# raspi.net
KiCad netlist of a schematic drawn in EAGLE
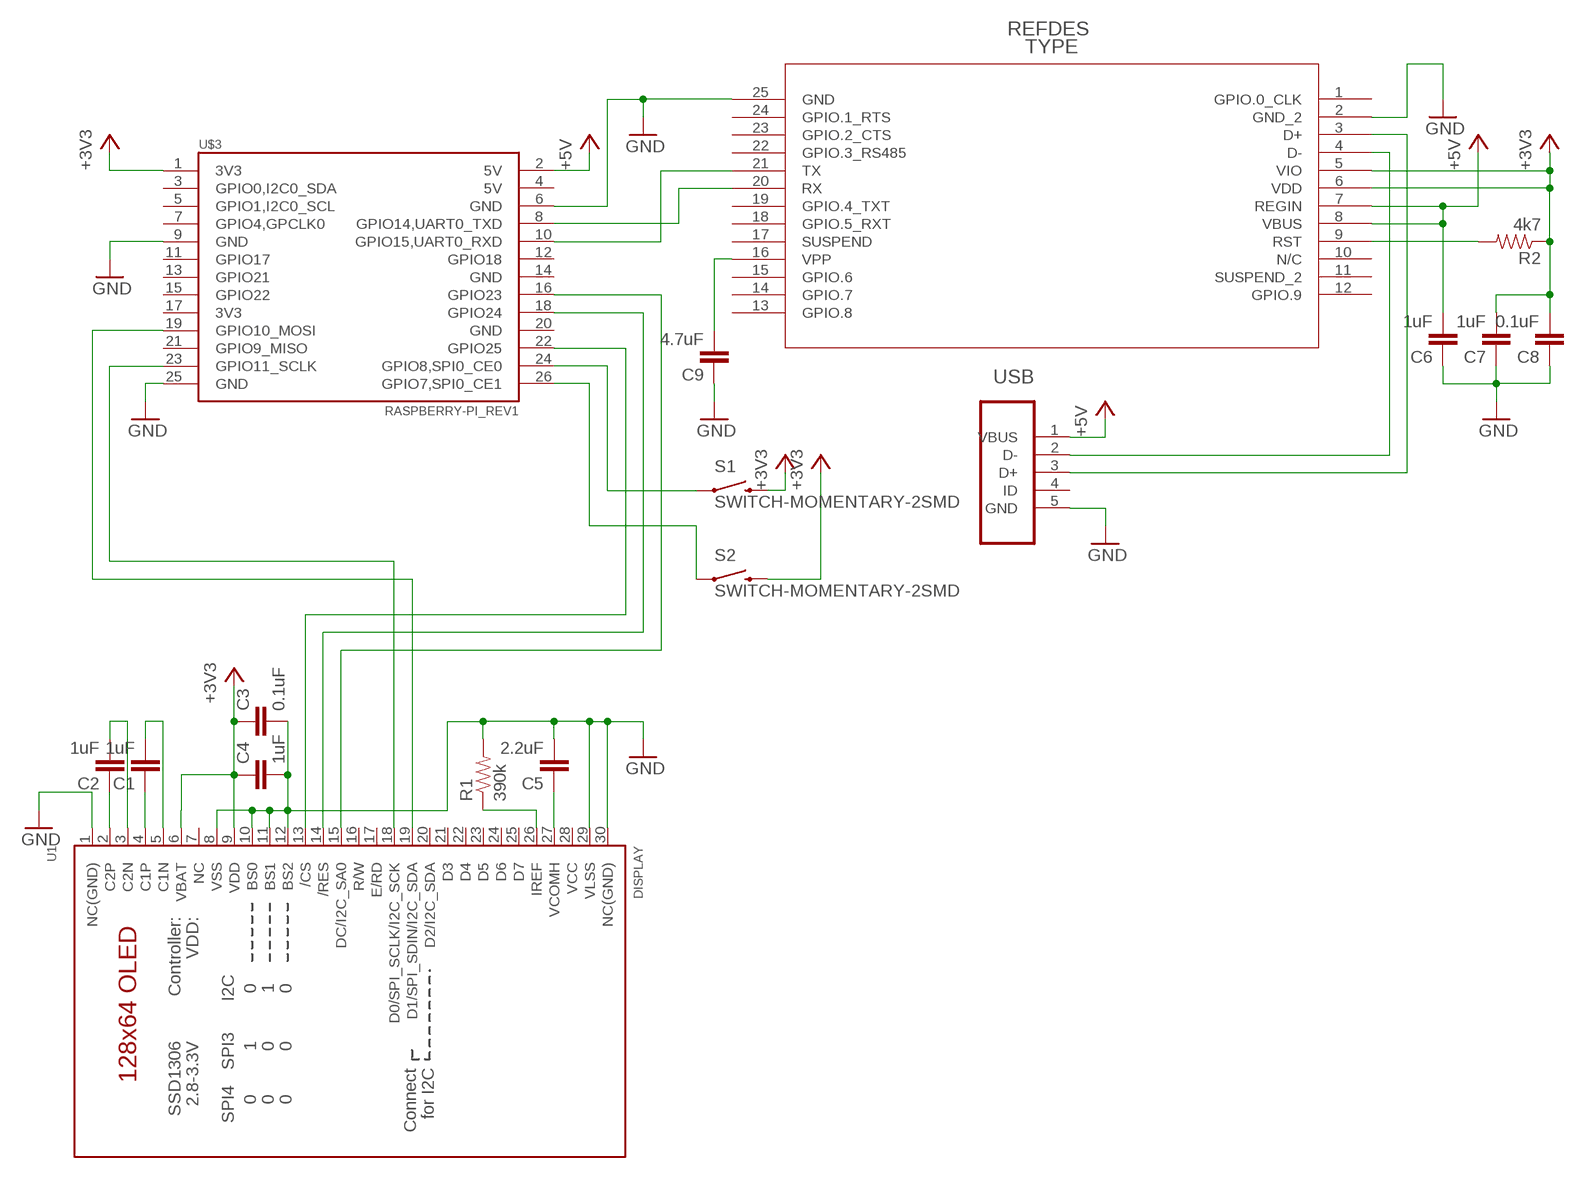
[diagram p0: schematic, sheet 1]

(export (version "E")
  (design (tool "Eeschema 10.0.6"))
  (components
    (comp (ref "C1")
      (value "1uF")
      (footprint "eagle-import:0805")
      (libsource (lib "eagle-import") (part "CAP0805"))
    )
    (comp (ref "C2")
      (value "1uF")
      (footprint "eagle-import:0805")
      (libsource (lib "eagle-import") (part "CAP0805"))
    )
    (comp (ref "C3")
      (value "0.1uF")
      (footprint "eagle-import:0805")
      (libsource (lib "eagle-import") (part "CAP0805"))
    )
    (comp (ref "C4")
      (value "1uF")
      (footprint "eagle-import:0805")
      (libsource (lib "eagle-import") (part "CAP0805"))
    )
    (comp (ref "C5")
      (value "2.2uF")
      (footprint "eagle-import:0805")
      (libsource (lib "eagle-import") (part "CAP0805"))
    )
    (comp (ref "C6")
      (value "1uF")
      (footprint "eagle-import:0805")
      (libsource (lib "eagle-import") (part "CAP0805"))
    )
    (comp (ref "C7")
      (value "1uF")
      (footprint "eagle-import:0805")
      (libsource (lib "eagle-import") (part "CAP0805"))
    )
    (comp (ref "C8")
      (value "0.1uF")
      (footprint "eagle-import:0805")
      (libsource (lib "eagle-import") (part "CAP0805"))
    )
    (comp (ref "C9")
      (value "4.7uF")
      (footprint "eagle-import:0805")
      (libsource (lib "eagle-import") (part "CAP0805"))
    )
    (comp (ref "R1")
      (value "390k")
      (footprint "eagle-import:0805")
      (libsource (lib "eagle-import") (part "RESISTOR0805-RES"))
    )
    (comp (ref "R2")
      (value "4k7")
      (footprint "eagle-import:0805")
      (libsource (lib "eagle-import") (part "RESISTOR0805-RES"))
    )
    (comp (ref "S1")
      (value "SWITCH-MOMENTARY-2SMD")
      (footprint "eagle-import:TACTILE_SWITCH_SMD")
      (libsource (lib "eagle-import") (part "SWITCH-MOMENTARY-2SMD"))
    )
    (comp (ref "S2")
      (value "SWITCH-MOMENTARY-2SMD")
      (footprint "eagle-import:TACTILE_SWITCH_SMD")
      (libsource (lib "eagle-import") (part "SWITCH-MOMENTARY-2SMD"))
    )
    (comp (ref "U$3")
      (value "RASPBERRY-PI_REV1")
      (footprint "eagle-import:RASPBERRY-PI_REV1")
      (libsource (lib "eagle-import") (part "RASPBERRY-PI_REV1"))
    )
    (comp (ref "U1")
      (value "DISPLAY")
      (footprint "eagle-import:UG-2864HSWEG01_0.96IN_WRAPAROUND")
      (libsource (lib "eagle-import") (part "DISP_OLED_UG-2864HSWEG010.96{dblquote}"))
    )
    (comp (ref "U2")
      (value "CP2110-F01-GM")
      (footprint "eagle-import:CP2110-F01-GM")
      (libsource (lib "eagle-import") (part "CP2110-F01-GM"))
    )
    (comp (ref "USB")
      (value "47346-0001")
      (footprint "eagle-import:MOLEX_47346-0001")
      (libsource (lib "eagle-import") (part "47346-0001"))
    )
  )
  (nets
    (net (code "1") (name "+3V3") (class "Default")
      (node (ref "C3") (pin "1") (pinfunction "1_1") (pintype "passive"))
      (node (ref "C4") (pin "1") (pinfunction "1_1") (pintype "passive"))
      (node (ref "C7") (pin "2") (pinfunction "2_2") (pintype "passive"))
      (node (ref "C8") (pin "2") (pinfunction "2_2") (pintype "passive"))
      (node (ref "R2") (pin "1") (pinfunction "1_1") (pintype "passive"))
      (node (ref "S1") (pin "3") (pinfunction "2_3") (pintype "passive"))
      (node (ref "S2") (pin "3") (pinfunction "2_3") (pintype "passive"))
      (node (ref "U$3") (pin "1") (pinfunction "3V3_1") (pintype "bidirectional"))
      (node (ref "U1") (pin "6") (pinfunction "VBAT_6") (pintype "input"))
      (node (ref "U1") (pin "9") (pinfunction "VDD_9") (pintype "power_in"))
      (node (ref "U2") (pin "5") (pinfunction "VIO_5") (pintype "passive"))
      (node (ref "U2") (pin "6") (pinfunction "VDD_6") (pintype "passive"))
    )
    (net (code "2") (name "+5V") (class "Default")
      (node (ref "C6") (pin "2") (pinfunction "2_2") (pintype "passive"))
      (node (ref "U$3") (pin "2") (pinfunction "5V_2") (pintype "bidirectional"))
      (node (ref "U2") (pin "7") (pinfunction "REGIN_7") (pintype "passive"))
      (node (ref "U2") (pin "8") (pinfunction "VBUS_8") (pintype "passive"))
      (node (ref "USB") (pin "1") (pinfunction "VBUS_1") (pintype "input"))
    )
    (net (code "3") (name "/VCC") (class "Default")
      (node (ref "U1") (pin "28") (pinfunction "VCC_28") (pintype "power_in"))
    )
    (net (code "4") (name "GND") (class "Default")
      (node (ref "C3") (pin "2") (pinfunction "2_2") (pintype "passive"))
      (node (ref "C4") (pin "2") (pinfunction "2_2") (pintype "passive"))
      (node (ref "C5") (pin "2") (pinfunction "2_2") (pintype "passive"))
      (node (ref "C6") (pin "1") (pinfunction "1_1") (pintype "passive"))
      (node (ref "C7") (pin "1") (pinfunction "1_1") (pintype "passive"))
      (node (ref "C8") (pin "1") (pinfunction "1_1") (pintype "passive"))
      (node (ref "C9") (pin "1") (pinfunction "1_1") (pintype "passive"))
      (node (ref "R1") (pin "2") (pinfunction "2_2") (pintype "passive"))
      (node (ref "U$3") (pin "25") (pinfunction "GND_25") (pintype "bidirectional"))
      (node (ref "U$3") (pin "6") (pinfunction "GND_6") (pintype "bidirectional"))
      (node (ref "U$3") (pin "9") (pinfunction "GND_9") (pintype "bidirectional"))
      (node (ref "U1") (pin "1") (pinfunction "NC(GND)_1") (pintype "input"))
      (node (ref "U1") (pin "10") (pinfunction "BS0_10") (pintype "input"))
      (node (ref "U1") (pin "11") (pinfunction "BS1_11") (pintype "input"))
      (node (ref "U1") (pin "12") (pinfunction "BS2_12") (pintype "input"))
      (node (ref "U1") (pin "29") (pinfunction "VLSS_29") (pintype "power_in"))
      (node (ref "U1") (pin "30") (pinfunction "NC(GND)_30") (pintype "input"))
      (node (ref "U1") (pin "8") (pinfunction "VSS_8") (pintype "power_in"))
      (node (ref "U2") (pin "2") (pinfunction "GND_2_2") (pintype "passive"))
      (node (ref "U2") (pin "25") (pinfunction "GND_25") (pintype "passive"))
      (node (ref "USB") (pin "5") (pinfunction "GND_5") (pintype "input"))
    )
    (net (code "5") (name "Net-(U$3-GPIO7,SPI0_CE1)") (class "Default")
      (node (ref "S2") (pin "1") (pinfunction "1_1") (pintype "passive"))
      (node (ref "U$3") (pin "26") (pinfunction "GPIO7,SPI0_CE1_26") (pintype "bidirectional"))
    )
    (net (code "6") (name "Net-(U$3-GPIO8,SPI0_CE0)") (class "Default")
      (node (ref "S1") (pin "1") (pinfunction "1_1") (pintype "passive"))
      (node (ref "U$3") (pin "24") (pinfunction "GPIO8,SPI0_CE0_24") (pintype "bidirectional"))
    )
    (net (code "7") (name "Net-(U$3-GPIO10_MOSI)") (class "Default")
      (node (ref "U$3") (pin "19") (pinfunction "GPIO10_MOSI_19") (pintype "bidirectional"))
      (node (ref "U1") (pin "19") (pinfunction "D1/SPI_SDIN/I2C_SDA_19") (pintype "bidirectional"))
    )
    (net (code "8") (name "Net-(U$3-GPIO11_SCLK)") (class "Default")
      (node (ref "U$3") (pin "23") (pinfunction "GPIO11_SCLK_23") (pintype "bidirectional"))
      (node (ref "U1") (pin "18") (pinfunction "D0/SPI_SCLK/I2C_SCK_18") (pintype "bidirectional"))
    )
    (net (code "9") (name "Net-(U$3-GPIO14,UART0_TXD)") (class "Default")
      (node (ref "U$3") (pin "8") (pinfunction "GPIO14,UART0_TXD_8") (pintype "bidirectional"))
      (node (ref "U2") (pin "20") (pinfunction "RX_20") (pintype "passive"))
    )
    (net (code "10") (name "Net-(U$3-GPIO15,UART0_RXD)") (class "Default")
      (node (ref "U$3") (pin "10") (pinfunction "GPIO15,UART0_RXD_10") (pintype "bidirectional"))
      (node (ref "U2") (pin "21") (pinfunction "TX_21") (pintype "passive"))
    )
    (net (code "11") (name "Net-(U$3-GPIO23)") (class "Default")
      (node (ref "U$3") (pin "16") (pinfunction "GPIO23_16") (pintype "bidirectional"))
      (node (ref "U1") (pin "15") (pinfunction "DC/I2C_SA0_15") (pintype "input"))
    )
    (net (code "12") (name "Net-(U$3-GPIO24)") (class "Default")
      (node (ref "U$3") (pin "18") (pinfunction "GPIO24_18") (pintype "bidirectional"))
      (node (ref "U1") (pin "14") (pinfunction "/RES_14") (pintype "input"))
    )
    (net (code "13") (name "Net-(U$3-GPIO25)") (class "Default")
      (node (ref "U$3") (pin "22") (pinfunction "GPIO25_22") (pintype "bidirectional"))
      (node (ref "U1") (pin "13") (pinfunction "/CS_13") (pintype "input"))
    )
    (net (code "14") (name "Net-(U1-C1N)") (class "Default")
      (node (ref "C1") (pin "2") (pinfunction "2_2") (pintype "passive"))
      (node (ref "U1") (pin "5") (pinfunction "C1N_5") (pintype "input"))
    )
    (net (code "15") (name "Net-(U1-C1P)") (class "Default")
      (node (ref "C1") (pin "1") (pinfunction "1_1") (pintype "passive"))
      (node (ref "U1") (pin "4") (pinfunction "C1P_4") (pintype "input"))
    )
    (net (code "16") (name "Net-(U1-C2N)") (class "Default")
      (node (ref "C2") (pin "2") (pinfunction "2_2") (pintype "passive"))
      (node (ref "U1") (pin "3") (pinfunction "C2N_3") (pintype "input"))
    )
    (net (code "17") (name "Net-(U1-C2P)") (class "Default")
      (node (ref "C2") (pin "1") (pinfunction "1_1") (pintype "passive"))
      (node (ref "U1") (pin "2") (pinfunction "C2P_2") (pintype "input"))
    )
    (net (code "18") (name "Net-(U1-IREF)") (class "Default")
      (node (ref "R1") (pin "1") (pinfunction "1_1") (pintype "passive"))
      (node (ref "U1") (pin "26") (pinfunction "IREF_26") (pintype "input"))
    )
    (net (code "19") (name "Net-(U1-VCOMH)") (class "Default")
      (node (ref "C5") (pin "1") (pinfunction "1_1") (pintype "passive"))
      (node (ref "U1") (pin "27") (pinfunction "VCOMH_27") (pintype "output"))
    )
    (net (code "20") (name "Net-(U2-D+)") (class "Default")
      (node (ref "U2") (pin "3") (pinfunction "D+_3") (pintype "passive"))
      (node (ref "USB") (pin "3") (pinfunction "D+_3") (pintype "input"))
    )
    (net (code "21") (name "Net-(U2-D-)") (class "Default")
      (node (ref "U2") (pin "4") (pinfunction "D-_4") (pintype "passive"))
      (node (ref "USB") (pin "2") (pinfunction "D-_2") (pintype "input"))
    )
    (net (code "22") (name "Net-(U2-RST)") (class "Default")
      (node (ref "R2") (pin "2") (pinfunction "2_2") (pintype "passive"))
      (node (ref "U2") (pin "9") (pinfunction "RST_9") (pintype "passive"))
    )
    (net (code "23") (name "Net-(U2-VPP)") (class "Default")
      (node (ref "C9") (pin "2") (pinfunction "2_2") (pintype "passive"))
      (node (ref "U2") (pin "16") (pinfunction "VPP_16") (pintype "passive"))
    )
    (net (code "24") (name "unconnected-(U$3-3V3-Pad17)") (class "Default")
      (node (ref "U$3") (pin "17") (pinfunction "3V3_17") (pintype "bidirectional"))
    )
    (net (code "25") (name "unconnected-(U$3-5V-Pad4)") (class "Default")
      (node (ref "U$3") (pin "4") (pinfunction "5V_4") (pintype "bidirectional"))
    )
    (net (code "26") (name "unconnected-(U$3-GND-Pad14)") (class "Default")
      (node (ref "U$3") (pin "14") (pinfunction "GND_14") (pintype "bidirectional"))
    )
    (net (code "27") (name "unconnected-(U$3-GND-Pad20)") (class "Default")
      (node (ref "U$3") (pin "20") (pinfunction "GND_20") (pintype "bidirectional"))
    )
    (net (code "28") (name "unconnected-(U$3-GPIO0,I2C0_SDA-Pad3)") (class "Default")
      (node (ref "U$3") (pin "3") (pinfunction "GPIO0,I2C0_SDA_3") (pintype "bidirectional"))
    )
    (net (code "29") (name "unconnected-(U$3-GPIO1,I2C0_SCL-Pad5)") (class "Default")
      (node (ref "U$3") (pin "5") (pinfunction "GPIO1,I2C0_SCL_5") (pintype "bidirectional"))
    )
    (net (code "30") (name "unconnected-(U$3-GPIO4,GPCLK0-Pad7)") (class "Default")
      (node (ref "U$3") (pin "7") (pinfunction "GPIO4,GPCLK0_7") (pintype "bidirectional"))
    )
    (net (code "31") (name "unconnected-(U$3-GPIO9_MISO-Pad21)") (class "Default")
      (node (ref "U$3") (pin "21") (pinfunction "GPIO9_MISO_21") (pintype "bidirectional"))
    )
    (net (code "32") (name "unconnected-(U$3-GPIO17-Pad11)") (class "Default")
      (node (ref "U$3") (pin "11") (pinfunction "GPIO17_11") (pintype "bidirectional"))
    )
    (net (code "33") (name "unconnected-(U$3-GPIO18-Pad12)") (class "Default")
      (node (ref "U$3") (pin "12") (pinfunction "GPIO18_12") (pintype "bidirectional"))
    )
    (net (code "34") (name "unconnected-(U$3-GPIO21-Pad13)") (class "Default")
      (node (ref "U$3") (pin "13") (pinfunction "GPIO21_13") (pintype "bidirectional"))
    )
    (net (code "35") (name "unconnected-(U$3-GPIO22-Pad15)") (class "Default")
      (node (ref "U$3") (pin "15") (pinfunction "GPIO22_15") (pintype "bidirectional"))
    )
    (net (code "36") (name "unconnected-(U1-D2{slash}I2C_SDA-Pad20)") (class "Default")
      (node (ref "U1") (pin "20") (pinfunction "D2/I2C_SDA_20") (pintype "bidirectional"))
    )
    (net (code "37") (name "unconnected-(U1-D3-Pad21)") (class "Default")
      (node (ref "U1") (pin "21") (pinfunction "D3_21") (pintype "bidirectional"))
    )
    (net (code "38") (name "unconnected-(U1-D4-Pad22)") (class "Default")
      (node (ref "U1") (pin "22") (pinfunction "D4_22") (pintype "bidirectional"))
    )
    (net (code "39") (name "unconnected-(U1-D5-Pad23)") (class "Default")
      (node (ref "U1") (pin "23") (pinfunction "D5_23") (pintype "bidirectional"))
    )
    (net (code "40") (name "unconnected-(U1-D6-Pad24)") (class "Default")
      (node (ref "U1") (pin "24") (pinfunction "D6_24") (pintype "bidirectional"))
    )
    (net (code "41") (name "unconnected-(U1-D7-Pad25)") (class "Default")
      (node (ref "U1") (pin "25") (pinfunction "D7_25") (pintype "bidirectional"))
    )
    (net (code "42") (name "unconnected-(U1-E{slash}RD-Pad17)") (class "Default")
      (node (ref "U1") (pin "17") (pinfunction "E/RD_17") (pintype "input"))
    )
    (net (code "43") (name "unconnected-(U1-NC-Pad7)") (class "Default")
      (node (ref "U1") (pin "7") (pinfunction "NC_7") (pintype "no_connect"))
    )
    (net (code "44") (name "unconnected-(U1-R{slash}W-Pad16)") (class "Default")
      (node (ref "U1") (pin "16") (pinfunction "R/W_16") (pintype "input"))
    )
    (net (code "45") (name "unconnected-(U2-GPIO.0_CLK-Pad1)") (class "Default")
      (node (ref "U2") (pin "1") (pinfunction "GPIO.0_CLK_1") (pintype "passive"))
    )
    (net (code "46") (name "unconnected-(U2-GPIO.1_RTS-Pad24)") (class "Default")
      (node (ref "U2") (pin "24") (pinfunction "GPIO.1_RTS_24") (pintype "passive"))
    )
    (net (code "47") (name "unconnected-(U2-GPIO.2_CTS-Pad23)") (class "Default")
      (node (ref "U2") (pin "23") (pinfunction "GPIO.2_CTS_23") (pintype "passive"))
    )
    (net (code "48") (name "unconnected-(U2-GPIO.3_RS485-Pad22)") (class "Default")
      (node (ref "U2") (pin "22") (pinfunction "GPIO.3_RS485_22") (pintype "passive"))
    )
    (net (code "49") (name "unconnected-(U2-GPIO.4_TXT-Pad19)") (class "Default")
      (node (ref "U2") (pin "19") (pinfunction "GPIO.4_TXT_19") (pintype "passive"))
    )
    (net (code "50") (name "unconnected-(U2-GPIO.5_RXT-Pad18)") (class "Default")
      (node (ref "U2") (pin "18") (pinfunction "GPIO.5_RXT_18") (pintype "passive"))
    )
    (net (code "51") (name "unconnected-(U2-GPIO.6-Pad15)") (class "Default")
      (node (ref "U2") (pin "15") (pinfunction "GPIO.6_15") (pintype "passive"))
    )
    (net (code "52") (name "unconnected-(U2-GPIO.7-Pad14)") (class "Default")
      (node (ref "U2") (pin "14") (pinfunction "GPIO.7_14") (pintype "passive"))
    )
    (net (code "53") (name "unconnected-(U2-GPIO.8-Pad13)") (class "Default")
      (node (ref "U2") (pin "13") (pinfunction "GPIO.8_13") (pintype "passive"))
    )
    (net (code "54") (name "unconnected-(U2-GPIO.9-Pad12)") (class "Default")
      (node (ref "U2") (pin "12") (pinfunction "GPIO.9_12") (pintype "passive"))
    )
    (net (code "55") (name "unconnected-(U2-N{slash}C-Pad10)") (class "Default")
      (node (ref "U2") (pin "10") (pinfunction "N/C_10") (pintype "passive"))
    )
    (net (code "56") (name "unconnected-(U2-SUSPEND-Pad17)") (class "Default")
      (node (ref "U2") (pin "17") (pinfunction "SUSPEND_17") (pintype "passive"))
    )
    (net (code "57") (name "unconnected-(U2-SUSPEND_2-Pad11)") (class "Default")
      (node (ref "U2") (pin "11") (pinfunction "SUSPEND_2_11") (pintype "passive"))
    )
    (net (code "58") (name "unconnected-(USB-ID-Pad4)") (class "Default")
      (node (ref "USB") (pin "4") (pinfunction "ID_4") (pintype "input"))
    )
  )
)
